# 07_DADC.net
KiCad netlist of a schematic drawn in Altium Designer
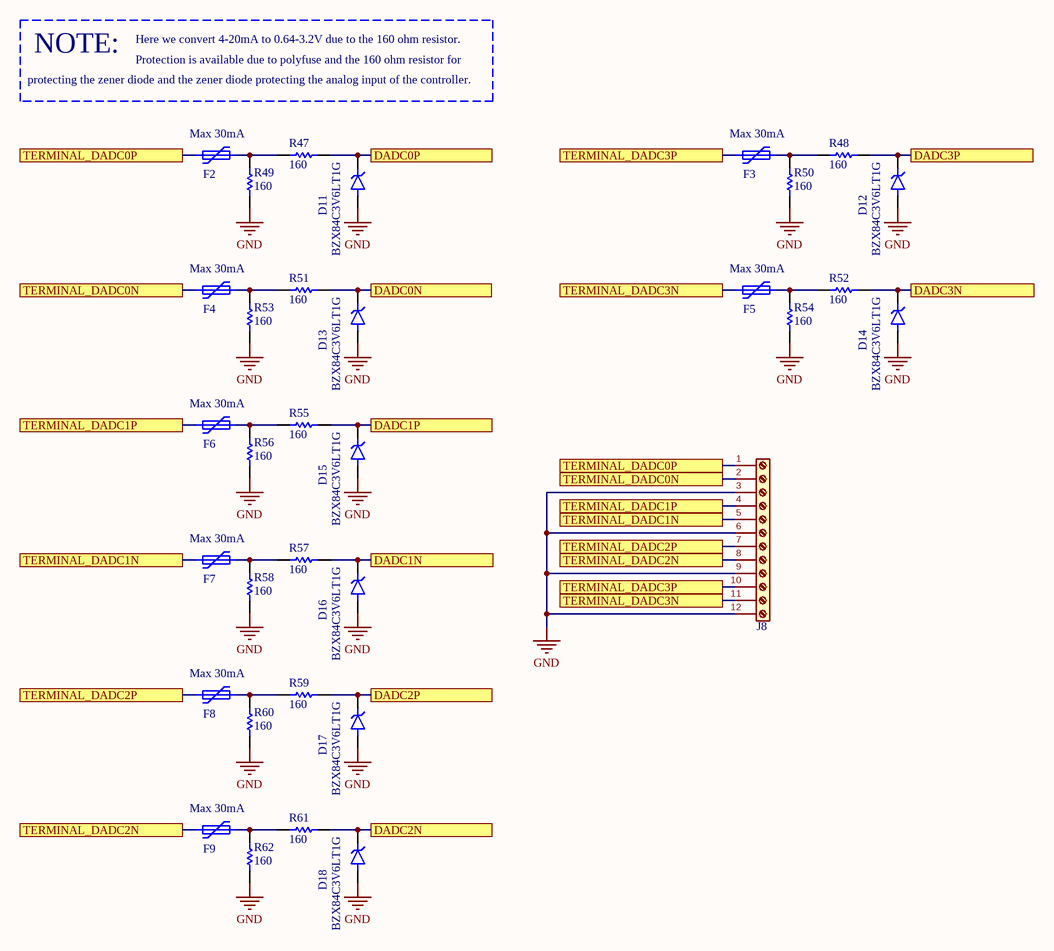
[diagram p0: 07_DADC.SchDoc]

(export (version "E")
  (design (tool "Eeschema 10.0.6"))
  (components
    (comp (ref "D11")
      (value "BZX84C3V6LT1G")
      (footprint "SOT95P240X111-3N")
      (fields (field (name "MP") "BZX84C10LT1G"))
      (libsource (lib "PROC051C_AWR1843BOOST_RevC") (part "BZX84C3V6LT1G"))
    )
    (comp (ref "D12")
      (value "BZX84C3V6LT1G")
      (footprint "SOT95P240X111-3N")
      (fields (field (name "MP") "BZX84C10LT1G"))
      (libsource (lib "PROC051C_AWR1843BOOST_RevC") (part "BZX84C3V6LT1G"))
    )
    (comp (ref "D13")
      (value "BZX84C3V6LT1G")
      (footprint "SOT95P240X111-3N")
      (fields (field (name "MP") "BZX84C10LT1G"))
      (libsource (lib "PROC051C_AWR1843BOOST_RevC") (part "BZX84C3V6LT1G"))
    )
    (comp (ref "D14")
      (value "BZX84C3V6LT1G")
      (footprint "SOT95P240X111-3N")
      (fields (field (name "MP") "BZX84C10LT1G"))
      (libsource (lib "PROC051C_AWR1843BOOST_RevC") (part "BZX84C3V6LT1G"))
    )
    (comp (ref "D15")
      (value "BZX84C3V6LT1G")
      (footprint "SOT95P240X111-3N")
      (fields (field (name "MP") "BZX84C10LT1G"))
      (libsource (lib "PROC051C_AWR1843BOOST_RevC") (part "BZX84C3V6LT1G"))
    )
    (comp (ref "D16")
      (value "BZX84C3V6LT1G")
      (footprint "SOT95P240X111-3N")
      (fields (field (name "MP") "BZX84C10LT1G"))
      (libsource (lib "PROC051C_AWR1843BOOST_RevC") (part "BZX84C3V6LT1G"))
    )
    (comp (ref "D17")
      (value "BZX84C3V6LT1G")
      (footprint "SOT95P240X111-3N")
      (fields (field (name "MP") "BZX84C10LT1G"))
      (libsource (lib "PROC051C_AWR1843BOOST_RevC") (part "BZX84C3V6LT1G"))
    )
    (comp (ref "D18")
      (value "BZX84C3V6LT1G")
      (footprint "SOT95P240X111-3N")
      (fields (field (name "MP") "BZX84C10LT1G"))
      (libsource (lib "PROC051C_AWR1843BOOST_RevC") (part "BZX84C3V6LT1G"))
    )
    (comp (ref "F2")
      (value "Max 30mA")
      (footprint "Fuse_0603_1608Metric")
      (libsource (lib "PROC051C_AWR1843BOOST_RevC") (part "Polyfuse 0603"))
    )
    (comp (ref "F3")
      (value "Max 30mA")
      (footprint "Fuse_0603_1608Metric")
      (libsource (lib "PROC051C_AWR1843BOOST_RevC") (part "Polyfuse 0603"))
    )
    (comp (ref "F4")
      (value "Max 30mA")
      (footprint "Fuse_0603_1608Metric")
      (libsource (lib "PROC051C_AWR1843BOOST_RevC") (part "Polyfuse 0603"))
    )
    (comp (ref "F5")
      (value "Max 30mA")
      (footprint "Fuse_0603_1608Metric")
      (libsource (lib "PROC051C_AWR1843BOOST_RevC") (part "Polyfuse 0603"))
    )
    (comp (ref "F6")
      (value "Max 30mA")
      (footprint "Fuse_0603_1608Metric")
      (libsource (lib "PROC051C_AWR1843BOOST_RevC") (part "Polyfuse 0603"))
    )
    (comp (ref "F7")
      (value "Max 30mA")
      (footprint "Fuse_0603_1608Metric")
      (libsource (lib "PROC051C_AWR1843BOOST_RevC") (part "Polyfuse 0603"))
    )
    (comp (ref "F8")
      (value "Max 30mA")
      (footprint "Fuse_0603_1608Metric")
      (libsource (lib "PROC051C_AWR1843BOOST_RevC") (part "Polyfuse 0603"))
    )
    (comp (ref "F9")
      (value "Max 30mA")
      (footprint "Fuse_0603_1608Metric")
      (libsource (lib "PROC051C_AWR1843BOOST_RevC") (part "Polyfuse 0603"))
    )
    (comp (ref "J8")
      (value "Terminal_01x12_P5.00")
      (footprint "TerminalBlock_Phoenix_PT-1,5-12-5.0-H_1x12_P5.00mm_Horizontal")
      (libsource (lib "PROC051C_AWR1843BOOST_RevC") (part "Terminal_01x12_P5.00"))
    )
    (comp (ref "R47")
      (value "CRCW060320R0JNEA")
      (footprint "0603")
      (description "RES, 160, 5%, 0.1 W, AEC-Q200 Grade 0, 0603")
      (fields (field (name "MANUFACTURER") "Vishay-Dale") (field (name "VALUEDISPLAYED") "160"))
      (libsource (lib "PROC051C_AWR1843BOOST_RevC") (part "RES 160R 0603"))
    )
    (comp (ref "R48")
      (value "CRCW060320R0JNEA")
      (footprint "0603")
      (description "RES, 160, 5%, 0.1 W, AEC-Q200 Grade 0, 0603")
      (fields (field (name "MANUFACTURER") "Vishay-Dale") (field (name "VALUEDISPLAYED") "160"))
      (libsource (lib "PROC051C_AWR1843BOOST_RevC") (part "RES 160R 0603"))
    )
    (comp (ref "R49")
      (value "CRCW060320R0JNEA")
      (footprint "0603")
      (description "RES, 160, 5%, 0.1 W, AEC-Q200 Grade 0, 0603")
      (fields (field (name "MANUFACTURER") "Vishay-Dale") (field (name "VALUEDISPLAYED") "160"))
      (libsource (lib "PROC051C_AWR1843BOOST_RevC") (part "RES 160R 0603"))
    )
    (comp (ref "R50")
      (value "CRCW060320R0JNEA")
      (footprint "0603")
      (description "RES, 160, 5%, 0.1 W, AEC-Q200 Grade 0, 0603")
      (fields (field (name "MANUFACTURER") "Vishay-Dale") (field (name "VALUEDISPLAYED") "160"))
      (libsource (lib "PROC051C_AWR1843BOOST_RevC") (part "RES 160R 0603"))
    )
    (comp (ref "R51")
      (value "CRCW060320R0JNEA")
      (footprint "0603")
      (description "RES, 160, 5%, 0.1 W, AEC-Q200 Grade 0, 0603")
      (fields (field (name "MANUFACTURER") "Vishay-Dale") (field (name "VALUEDISPLAYED") "160"))
      (libsource (lib "PROC051C_AWR1843BOOST_RevC") (part "RES 160R 0603"))
    )
    (comp (ref "R52")
      (value "CRCW060320R0JNEA")
      (footprint "0603")
      (description "RES, 160, 5%, 0.1 W, AEC-Q200 Grade 0, 0603")
      (fields (field (name "MANUFACTURER") "Vishay-Dale") (field (name "VALUEDISPLAYED") "160"))
      (libsource (lib "PROC051C_AWR1843BOOST_RevC") (part "RES 160R 0603"))
    )
    (comp (ref "R53")
      (value "CRCW060320R0JNEA")
      (footprint "0603")
      (description "RES, 160, 5%, 0.1 W, AEC-Q200 Grade 0, 0603")
      (fields (field (name "MANUFACTURER") "Vishay-Dale") (field (name "VALUEDISPLAYED") "160"))
      (libsource (lib "PROC051C_AWR1843BOOST_RevC") (part "RES 160R 0603"))
    )
    (comp (ref "R54")
      (value "CRCW060320R0JNEA")
      (footprint "0603")
      (description "RES, 160, 5%, 0.1 W, AEC-Q200 Grade 0, 0603")
      (fields (field (name "MANUFACTURER") "Vishay-Dale") (field (name "VALUEDISPLAYED") "160"))
      (libsource (lib "PROC051C_AWR1843BOOST_RevC") (part "RES 160R 0603"))
    )
    (comp (ref "R55")
      (value "CRCW060320R0JNEA")
      (footprint "0603")
      (description "RES, 160, 5%, 0.1 W, AEC-Q200 Grade 0, 0603")
      (fields (field (name "MANUFACTURER") "Vishay-Dale") (field (name "VALUEDISPLAYED") "160"))
      (libsource (lib "PROC051C_AWR1843BOOST_RevC") (part "RES 160R 0603"))
    )
    (comp (ref "R56")
      (value "CRCW060320R0JNEA")
      (footprint "0603")
      (description "RES, 160, 5%, 0.1 W, AEC-Q200 Grade 0, 0603")
      (fields (field (name "MANUFACTURER") "Vishay-Dale") (field (name "VALUEDISPLAYED") "160"))
      (libsource (lib "PROC051C_AWR1843BOOST_RevC") (part "RES 160R 0603"))
    )
    (comp (ref "R57")
      (value "CRCW060320R0JNEA")
      (footprint "0603")
      (description "RES, 160, 5%, 0.1 W, AEC-Q200 Grade 0, 0603")
      (fields (field (name "MANUFACTURER") "Vishay-Dale") (field (name "VALUEDISPLAYED") "160"))
      (libsource (lib "PROC051C_AWR1843BOOST_RevC") (part "RES 160R 0603"))
    )
    (comp (ref "R58")
      (value "CRCW060320R0JNEA")
      (footprint "0603")
      (description "RES, 160, 5%, 0.1 W, AEC-Q200 Grade 0, 0603")
      (fields (field (name "MANUFACTURER") "Vishay-Dale") (field (name "VALUEDISPLAYED") "160"))
      (libsource (lib "PROC051C_AWR1843BOOST_RevC") (part "RES 160R 0603"))
    )
    (comp (ref "R59")
      (value "CRCW060320R0JNEA")
      (footprint "0603")
      (description "RES, 160, 5%, 0.1 W, AEC-Q200 Grade 0, 0603")
      (fields (field (name "MANUFACTURER") "Vishay-Dale") (field (name "VALUEDISPLAYED") "160"))
      (libsource (lib "PROC051C_AWR1843BOOST_RevC") (part "RES 160R 0603"))
    )
    (comp (ref "R60")
      (value "CRCW060320R0JNEA")
      (footprint "0603")
      (description "RES, 160, 5%, 0.1 W, AEC-Q200 Grade 0, 0603")
      (fields (field (name "MANUFACTURER") "Vishay-Dale") (field (name "VALUEDISPLAYED") "160"))
      (libsource (lib "PROC051C_AWR1843BOOST_RevC") (part "RES 160R 0603"))
    )
    (comp (ref "R61")
      (value "CRCW060320R0JNEA")
      (footprint "0603")
      (description "RES, 160, 5%, 0.1 W, AEC-Q200 Grade 0, 0603")
      (fields (field (name "MANUFACTURER") "Vishay-Dale") (field (name "VALUEDISPLAYED") "160"))
      (libsource (lib "PROC051C_AWR1843BOOST_RevC") (part "RES 160R 0603"))
    )
    (comp (ref "R62")
      (value "CRCW060320R0JNEA")
      (footprint "0603")
      (description "RES, 160, 5%, 0.1 W, AEC-Q200 Grade 0, 0603")
      (fields (field (name "MANUFACTURER") "Vishay-Dale") (field (name "VALUEDISPLAYED") "160"))
      (libsource (lib "PROC051C_AWR1843BOOST_RevC") (part "RES 160R 0603"))
    )
  )
  (nets
    (net (code "1") (name "/DADC0N") (class "Default")
      (node (ref "D13") (pin "3") (pinfunction "K_3") (pintype "passive"))
      (node (ref "R51") (pin "2") (pinfunction "2_2") (pintype "passive"))
    )
    (net (code "2") (name "/DADC0P") (class "Default")
      (node (ref "D11") (pin "3") (pinfunction "K_3") (pintype "passive"))
      (node (ref "R47") (pin "2") (pinfunction "2_2") (pintype "passive"))
    )
    (net (code "3") (name "/DADC1N") (class "Default")
      (node (ref "D16") (pin "3") (pinfunction "K_3") (pintype "passive"))
      (node (ref "R57") (pin "2") (pinfunction "2_2") (pintype "passive"))
    )
    (net (code "4") (name "/DADC1P") (class "Default")
      (node (ref "D15") (pin "3") (pinfunction "K_3") (pintype "passive"))
      (node (ref "R55") (pin "2") (pinfunction "2_2") (pintype "passive"))
    )
    (net (code "5") (name "/DADC2N") (class "Default")
      (node (ref "D18") (pin "3") (pinfunction "K_3") (pintype "passive"))
      (node (ref "R61") (pin "2") (pinfunction "2_2") (pintype "passive"))
    )
    (net (code "6") (name "/DADC2P") (class "Default")
      (node (ref "D17") (pin "3") (pinfunction "K_3") (pintype "passive"))
      (node (ref "R59") (pin "2") (pinfunction "2_2") (pintype "passive"))
    )
    (net (code "7") (name "/DADC3N") (class "Default")
      (node (ref "D14") (pin "3") (pinfunction "K_3") (pintype "passive"))
      (node (ref "R52") (pin "2") (pinfunction "2_2") (pintype "passive"))
    )
    (net (code "8") (name "/DADC3P") (class "Default")
      (node (ref "D12") (pin "3") (pinfunction "K_3") (pintype "passive"))
      (node (ref "R48") (pin "2") (pinfunction "2_2") (pintype "passive"))
    )
    (net (code "9") (name "/TERMINAL_DADC0N") (class "Default")
      (node (ref "F4") (pin "1") (pinfunction "1_1") (pintype "passive"))
      (node (ref "J8") (pin "2") (pinfunction "Pin_2_2") (pintype "passive"))
    )
    (net (code "10") (name "/TERMINAL_DADC0P") (class "Default")
      (node (ref "F2") (pin "1") (pinfunction "1_1") (pintype "passive"))
      (node (ref "J8") (pin "1") (pinfunction "Pin_1_1") (pintype "passive"))
    )
    (net (code "11") (name "/TERMINAL_DADC1N") (class "Default")
      (node (ref "F7") (pin "1") (pinfunction "1_1") (pintype "passive"))
      (node (ref "J8") (pin "5") (pinfunction "Pin_5_5") (pintype "passive"))
    )
    (net (code "12") (name "/TERMINAL_DADC1P") (class "Default")
      (node (ref "F6") (pin "1") (pinfunction "1_1") (pintype "passive"))
      (node (ref "J8") (pin "4") (pinfunction "Pin_4_4") (pintype "passive"))
    )
    (net (code "13") (name "/TERMINAL_DADC2N") (class "Default")
      (node (ref "F9") (pin "1") (pinfunction "1_1") (pintype "passive"))
      (node (ref "J8") (pin "8") (pinfunction "Pin_8_8") (pintype "passive"))
    )
    (net (code "14") (name "/TERMINAL_DADC2P") (class "Default")
      (node (ref "F8") (pin "1") (pinfunction "1_1") (pintype "passive"))
      (node (ref "J8") (pin "7") (pinfunction "Pin_7_7") (pintype "passive"))
    )
    (net (code "15") (name "/TERMINAL_DADC3N") (class "Default")
      (node (ref "F5") (pin "1") (pinfunction "1_1") (pintype "passive"))
      (node (ref "J8") (pin "11") (pinfunction "Pin_11_11") (pintype "passive"))
    )
    (net (code "16") (name "/TERMINAL_DADC3P") (class "Default")
      (node (ref "F3") (pin "1") (pinfunction "1_1") (pintype "passive"))
      (node (ref "J8") (pin "10") (pinfunction "Pin_10_10") (pintype "passive"))
    )
    (net (code "17") (name "GND") (class "Default")
      (node (ref "D11") (pin "1") (pinfunction "A_1") (pintype "passive"))
      (node (ref "D12") (pin "1") (pinfunction "A_1") (pintype "passive"))
      (node (ref "D13") (pin "1") (pinfunction "A_1") (pintype "passive"))
      (node (ref "D14") (pin "1") (pinfunction "A_1") (pintype "passive"))
      (node (ref "D15") (pin "1") (pinfunction "A_1") (pintype "passive"))
      (node (ref "D16") (pin "1") (pinfunction "A_1") (pintype "passive"))
      (node (ref "D17") (pin "1") (pinfunction "A_1") (pintype "passive"))
      (node (ref "D18") (pin "1") (pinfunction "A_1") (pintype "passive"))
      (node (ref "J8") (pin "12") (pinfunction "Pin_12_12") (pintype "passive"))
      (node (ref "J8") (pin "3") (pinfunction "Pin_3_3") (pintype "passive"))
      (node (ref "J8") (pin "6") (pinfunction "Pin_6_6") (pintype "passive"))
      (node (ref "J8") (pin "9") (pinfunction "Pin_9_9") (pintype "passive"))
      (node (ref "R49") (pin "1") (pinfunction "1_1") (pintype "passive"))
      (node (ref "R50") (pin "1") (pinfunction "1_1") (pintype "passive"))
      (node (ref "R53") (pin "1") (pinfunction "1_1") (pintype "passive"))
      (node (ref "R54") (pin "1") (pinfunction "1_1") (pintype "passive"))
      (node (ref "R56") (pin "1") (pinfunction "1_1") (pintype "passive"))
      (node (ref "R58") (pin "1") (pinfunction "1_1") (pintype "passive"))
      (node (ref "R60") (pin "1") (pinfunction "1_1") (pintype "passive"))
      (node (ref "R62") (pin "1") (pinfunction "1_1") (pintype "passive"))
    )
    (net (code "18") (name "Net-(F2-Pad2)") (class "Default")
      (node (ref "F2") (pin "2") (pinfunction "2_2") (pintype "passive"))
      (node (ref "R47") (pin "1") (pinfunction "1_1") (pintype "passive"))
      (node (ref "R49") (pin "2") (pinfunction "2_2") (pintype "passive"))
    )
    (net (code "19") (name "Net-(F3-Pad2)") (class "Default")
      (node (ref "F3") (pin "2") (pinfunction "2_2") (pintype "passive"))
      (node (ref "R48") (pin "1") (pinfunction "1_1") (pintype "passive"))
      (node (ref "R50") (pin "2") (pinfunction "2_2") (pintype "passive"))
    )
    (net (code "20") (name "Net-(F4-Pad2)") (class "Default")
      (node (ref "F4") (pin "2") (pinfunction "2_2") (pintype "passive"))
      (node (ref "R51") (pin "1") (pinfunction "1_1") (pintype "passive"))
      (node (ref "R53") (pin "2") (pinfunction "2_2") (pintype "passive"))
    )
    (net (code "21") (name "Net-(F5-Pad2)") (class "Default")
      (node (ref "F5") (pin "2") (pinfunction "2_2") (pintype "passive"))
      (node (ref "R52") (pin "1") (pinfunction "1_1") (pintype "passive"))
      (node (ref "R54") (pin "2") (pinfunction "2_2") (pintype "passive"))
    )
    (net (code "22") (name "Net-(F6-Pad2)") (class "Default")
      (node (ref "F6") (pin "2") (pinfunction "2_2") (pintype "passive"))
      (node (ref "R55") (pin "1") (pinfunction "1_1") (pintype "passive"))
      (node (ref "R56") (pin "2") (pinfunction "2_2") (pintype "passive"))
    )
    (net (code "23") (name "Net-(F7-Pad2)") (class "Default")
      (node (ref "F7") (pin "2") (pinfunction "2_2") (pintype "passive"))
      (node (ref "R57") (pin "1") (pinfunction "1_1") (pintype "passive"))
      (node (ref "R58") (pin "2") (pinfunction "2_2") (pintype "passive"))
    )
    (net (code "24") (name "Net-(F8-Pad2)") (class "Default")
      (node (ref "F8") (pin "2") (pinfunction "2_2") (pintype "passive"))
      (node (ref "R59") (pin "1") (pinfunction "1_1") (pintype "passive"))
      (node (ref "R60") (pin "2") (pinfunction "2_2") (pintype "passive"))
    )
    (net (code "25") (name "Net-(F9-Pad2)") (class "Default")
      (node (ref "F9") (pin "2") (pinfunction "2_2") (pintype "passive"))
      (node (ref "R61") (pin "1") (pinfunction "1_1") (pintype "passive"))
      (node (ref "R62") (pin "2") (pinfunction "2_2") (pintype "passive"))
    )
  )
)
